# 1_-SOM-G3399.net
KiCad netlist of a schematic drawn in Altium Designer
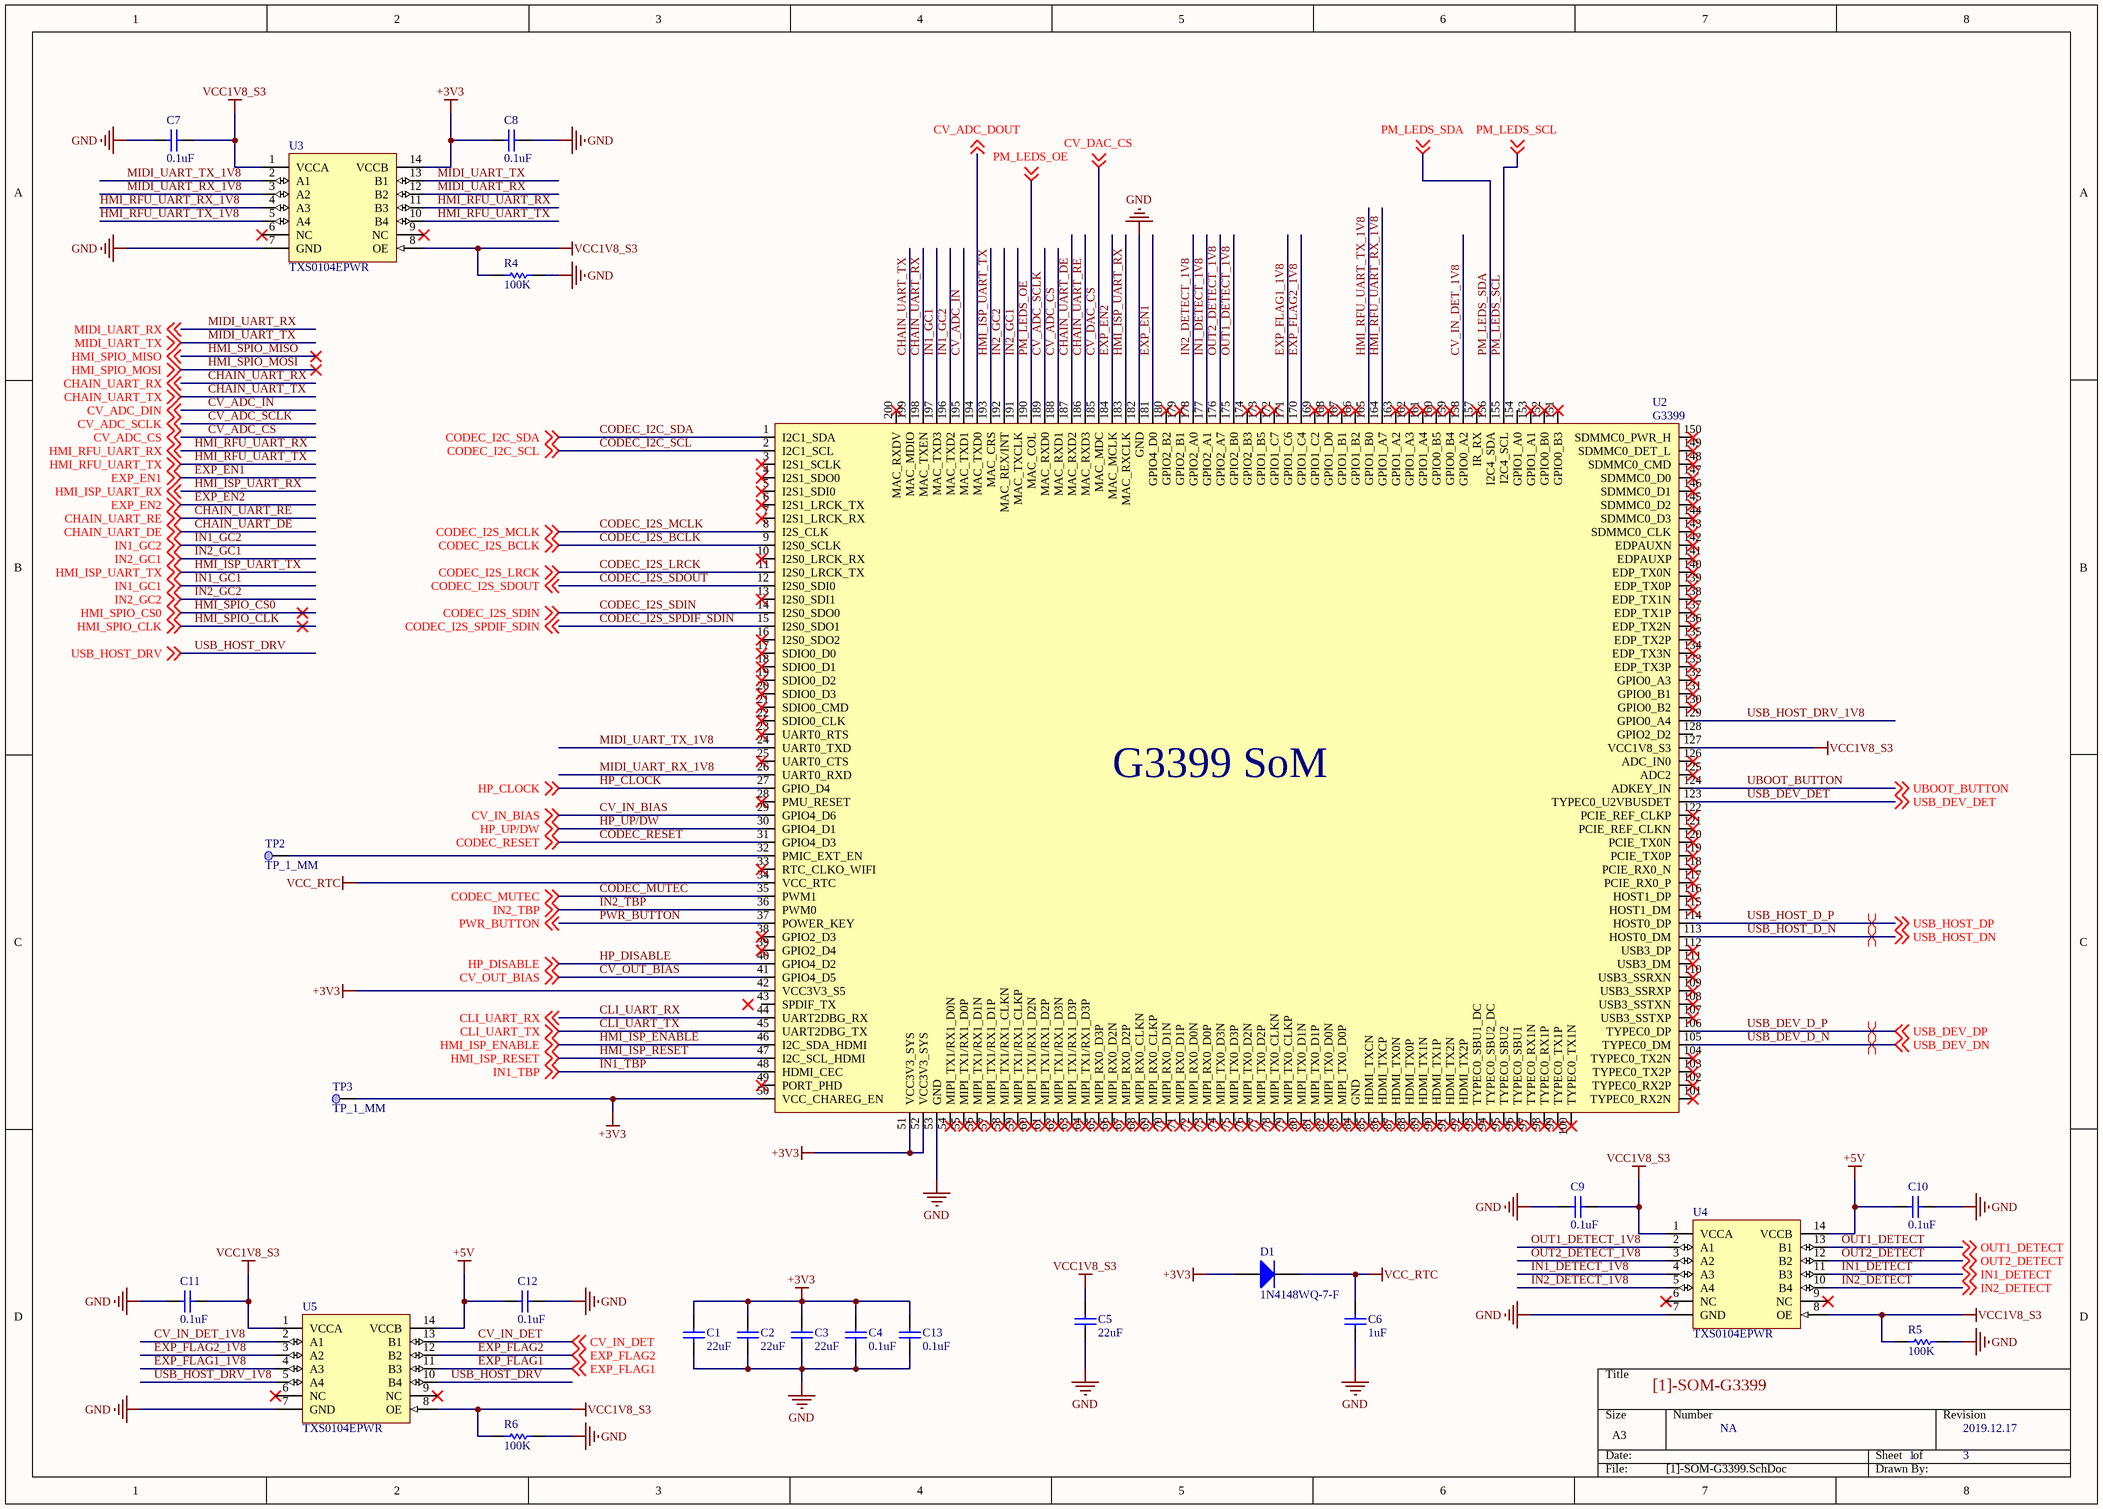
[diagram p0: [1]-SOM-G3399.SchDoc]

(export (version "E")
  (design (tool "Eeschema 10.0.6"))
  (components
    (comp (ref "C1")
      (value "22uF")
      (footprint "CAPC1608N")
      (description "CAP CER 22UF 6.3V X5R 0603")
      (fields (field (name "TOLERANCE") "20%"))
      (libsource (lib "bitsnio") (part "GRM188R60J226MEA0D"))
    )
    (comp (ref "C2")
      (value "22uF")
      (footprint "CAPC1608N")
      (description "CAP CER 22UF 6.3V X5R 0603")
      (fields (field (name "TOLERANCE") "20%"))
      (libsource (lib "bitsnio") (part "GRM188R60J226MEA0D"))
    )
    (comp (ref "C3")
      (value "22uF")
      (footprint "CAPC1608N")
      (description "CAP CER 22UF 6.3V X5R 0603")
      (fields (field (name "TOLERANCE") "20%"))
      (libsource (lib "bitsnio") (part "GRM188R60J226MEA0D"))
    )
    (comp (ref "C4")
      (value "0.1uF")
      (footprint "CAPC1005N")
      (description "CAP CER 0.1UF 50V X7R 0402")
      (fields (field (name "TOLERANCE") "10 %"))
      (libsource (lib "bitsnio") (part "GRM155R71H104KE14D"))
    )
    (comp (ref "C5")
      (value "22uF")
      (footprint "CAPC1608N")
      (description "CAP CER 22UF 6.3V X5R 0603")
      (fields (field (name "TOLERANCE") "20%"))
      (libsource (lib "bitsnio") (part "GRM188R60J226MEA0D"))
    )
    (comp (ref "C6")
      (value "1uF")
      (footprint "CAPC1005N")
      (description "CAP CER 1UF 6.3V X5R 0402")
      (fields (field (name "TOLERANCE") "±10%"))
      (libsource (lib "bitsnio") (part "C0402C105K9PACTU"))
    )
    (comp (ref "C7")
      (value "0.1uF")
      (footprint "CAPC1005N")
      (description "CAP CER 0.1UF 50V X7R 0402")
      (fields (field (name "TOLERANCE") "10 %"))
      (libsource (lib "bitsnio") (part "GRM155R71H104KE14D"))
    )
    (comp (ref "C8")
      (value "0.1uF")
      (footprint "CAPC1005N")
      (description "CAP CER 0.1UF 50V X7R 0402")
      (fields (field (name "TOLERANCE") "10 %"))
      (libsource (lib "bitsnio") (part "GRM155R71H104KE14D"))
    )
    (comp (ref "C9")
      (value "0.1uF")
      (footprint "CAPC1005N")
      (description "CAP CER 0.1UF 50V X7R 0402")
      (fields (field (name "TOLERANCE") "10 %"))
      (libsource (lib "bitsnio") (part "GRM155R71H104KE14D"))
    )
    (comp (ref "C10")
      (value "0.1uF")
      (footprint "CAPC1005N")
      (description "CAP CER 0.1UF 50V X7R 0402")
      (fields (field (name "TOLERANCE") "10 %"))
      (libsource (lib "bitsnio") (part "GRM155R71H104KE14D"))
    )
    (comp (ref "C11")
      (value "0.1uF")
      (footprint "CAPC1005N")
      (description "CAP CER 0.1UF 50V X7R 0402")
      (fields (field (name "TOLERANCE") "10 %"))
      (libsource (lib "bitsnio") (part "GRM155R71H104KE14D"))
    )
    (comp (ref "C12")
      (value "0.1uF")
      (footprint "CAPC1005N")
      (description "CAP CER 0.1UF 50V X7R 0402")
      (fields (field (name "TOLERANCE") "10 %"))
      (libsource (lib "bitsnio") (part "GRM155R71H104KE14D"))
    )
    (comp (ref "C13")
      (value "0.1uF")
      (footprint "CAPC1005N")
      (description "CAP CER 0.1UF 50V X7R 0402")
      (fields (field (name "TOLERANCE") "10 %"))
      (libsource (lib "bitsnio") (part "GRM155R71H104KE14D"))
    )
    (comp (ref "D1")
      (value "1N4148WQ-7-F")
      (footprint "SOD123")
      (description "DIODE GEN PURP 100V 300MA SOD123")
      (libsource (lib "bitsnio") (part "1N4148WQ-7-F"))
    )
    (comp (ref "R4")
      (value "100K")
      (footprint "RESC1005N")
      (description "RES SMD 100K OHM 1% 1/16W 0402")
      (fields (field (name "TOLERANCE") "1 %"))
      (libsource (lib "bitsnio") (part "RC0402FR-07100KL"))
    )
    (comp (ref "R5")
      (value "100K")
      (footprint "RESC1005N")
      (description "RES SMD 100K OHM 1% 1/16W 0402")
      (fields (field (name "TOLERANCE") "1 %"))
      (libsource (lib "bitsnio") (part "RC0402FR-07100KL"))
    )
    (comp (ref "R6")
      (value "100K")
      (footprint "RESC1005N")
      (description "RES SMD 100K OHM 1% 1/16W 0402")
      (fields (field (name "TOLERANCE") "1 %"))
      (libsource (lib "bitsnio") (part "RC0402FR-07100KL"))
    )
    (comp (ref "TP2") (value "TP_1_MM") (footprint "TP_1_MM") (libsource (lib "bitsnio") (part "TP_1_MM")))
    (comp (ref "TP3") (value "TP_1_MM") (footprint "TP_1_MM") (libsource (lib "bitsnio") (part "TP_1_MM")))
    (comp (ref "U2")
      (value "G3399")
      (footprint "G3399-MOD")
      (description "ROCKCHIP R3399 SoM")
      (libsource (lib "bitsnio") (part "G3399"))
    )
    (comp (ref "U3")
      (value "TXS0104EPWR")
      (footprint "TSSOP_PW14")
      (description "IC TRNSLTR BIDIRECTIONAL 14TSSOP")
      (libsource (lib "bitsnio") (part "IC_TXS0104EPWRG4"))
    )
    (comp (ref "U4")
      (value "TXS0104EPWR")
      (footprint "TSSOP_PW14")
      (description "IC TRNSLTR BIDIRECTIONAL 14TSSOP")
      (libsource (lib "bitsnio") (part "IC_TXS0104EPWRG4"))
    )
    (comp (ref "U5")
      (value "TXS0104EPWR")
      (footprint "TSSOP_PW14")
      (description "IC TRNSLTR BIDIRECTIONAL 14TSSOP")
      (libsource (lib "bitsnio") (part "IC_TXS0104EPWRG4"))
    )
  )
  (nets
    (net (code "1") (name "+3V3") (class "Default")
      (node (ref "C1") (pin "2") (pinfunction "2_2") (pintype "passive"))
      (node (ref "C13") (pin "2") (pinfunction "2_2") (pintype "passive"))
      (node (ref "C2") (pin "2") (pinfunction "2_2") (pintype "passive"))
      (node (ref "C3") (pin "2") (pinfunction "2_2") (pintype "passive"))
      (node (ref "C4") (pin "2") (pinfunction "2_2") (pintype "passive"))
      (node (ref "C8") (pin "2") (pinfunction "2_2") (pintype "passive"))
      (node (ref "D1") (pin "2") (pinfunction "A_2") (pintype "passive"))
      (node (ref "TP3") (pin "1") (pinfunction "1_1") (pintype "passive"))
      (node (ref "U2") (pin "42") (pinfunction "VCC3V3_S5_42") (pintype "passive"))
      (node (ref "U2") (pin "50") (pinfunction "VCC_CHAREG_EN_50") (pintype "passive"))
      (node (ref "U2") (pin "51") (pinfunction "VCC3V3_SYS_51") (pintype "passive"))
      (node (ref "U2") (pin "52") (pinfunction "VCC3V3_SYS_52") (pintype "passive"))
      (node (ref "U3") (pin "14") (pinfunction "VCCB_14") (pintype "power_in"))
    )
    (net (code "2") (name "+5V") (class "Default")
      (node (ref "C10") (pin "2") (pinfunction "2_2") (pintype "passive"))
      (node (ref "C12") (pin "2") (pinfunction "2_2") (pintype "passive"))
      (node (ref "U4") (pin "14") (pinfunction "VCCB_14") (pintype "power_in"))
      (node (ref "U5") (pin "14") (pinfunction "VCCB_14") (pintype "power_in"))
    )
    (net (code "3") (name "/CV_IN_DET_1V8") (class "Default")
      (node (ref "U2") (pin "158") (pinfunction "GPIO0_A2_158") (pintype "passive"))
      (node (ref "U5") (pin "2") (pinfunction "A1_2") (pintype "bidirectional"))
    )
    (net (code "4") (name "/EXP_FLAG1_1V8") (class "Default")
      (node (ref "U2") (pin "171") (pinfunction "GPIO1_C6_171") (pintype "passive"))
      (node (ref "U5") (pin "4") (pinfunction "A3_4") (pintype "bidirectional"))
    )
    (net (code "5") (name "/EXP_FLAG2_1V8") (class "Default")
      (node (ref "U2") (pin "170") (pinfunction "GPIO1_C4_170") (pintype "passive"))
      (node (ref "U5") (pin "3") (pinfunction "A2_3") (pintype "bidirectional"))
    )
    (net (code "6") (name "/HMI_RFU_UART_RX_1V8") (class "Default")
      (node (ref "U2") (pin "164") (pinfunction "GPIO1_A7_164") (pintype "passive"))
      (node (ref "U3") (pin "4") (pinfunction "A3_4") (pintype "bidirectional"))
    )
    (net (code "7") (name "/HMI_RFU_UART_TX_1V8") (class "Default")
      (node (ref "U2") (pin "165") (pinfunction "GPIO1_B0_165") (pintype "passive"))
      (node (ref "U3") (pin "5") (pinfunction "A4_5") (pintype "bidirectional"))
    )
    (net (code "8") (name "/IN1_DETECT_1V8") (class "Default")
      (node (ref "U2") (pin "177") (pinfunction "GPIO2_A1_177") (pintype "passive"))
      (node (ref "U4") (pin "4") (pinfunction "A3_4") (pintype "bidirectional"))
    )
    (net (code "9") (name "/IN2_DETECT_1V8") (class "Default")
      (node (ref "U2") (pin "178") (pinfunction "GPIO2_A0_178") (pintype "passive"))
      (node (ref "U4") (pin "5") (pinfunction "A4_5") (pintype "bidirectional"))
    )
    (net (code "10") (name "/MIDI_UART_RX_1V8") (class "Default")
      (node (ref "U2") (pin "26") (pinfunction "UART0_RXD_26") (pintype "passive"))
      (node (ref "U3") (pin "3") (pinfunction "A2_3") (pintype "bidirectional"))
    )
    (net (code "11") (name "/MIDI_UART_TX_1V8") (class "Default")
      (node (ref "U2") (pin "24") (pinfunction "UART0_TXD_24") (pintype "passive"))
      (node (ref "U3") (pin "2") (pinfunction "A1_2") (pintype "bidirectional"))
    )
    (net (code "12") (name "/OUT1_DETECT_1V8") (class "Default")
      (node (ref "U2") (pin "175") (pinfunction "GPIO2_B0_175") (pintype "passive"))
      (node (ref "U4") (pin "2") (pinfunction "A1_2") (pintype "bidirectional"))
    )
    (net (code "13") (name "/OUT2_DETECT_1V8") (class "Default")
      (node (ref "U2") (pin "176") (pinfunction "GPIO2_A7_176") (pintype "passive"))
      (node (ref "U4") (pin "3") (pinfunction "A2_3") (pintype "bidirectional"))
    )
    (net (code "14") (name "/USB_HOST_DRV_1V8") (class "Default")
      (node (ref "U2") (pin "129") (pinfunction "GPIO0_A4_129") (pintype "passive"))
      (node (ref "U5") (pin "5") (pinfunction "A4_5") (pintype "bidirectional"))
    )
    (net (code "15") (name "CHAIN_UART_DE") (class "Default")
      (node (ref "U2") (pin "187") (pinfunction "MAC_RXD2_187") (pintype "passive"))
    )
    (net (code "16") (name "CHAIN_UART_RE") (class "Default")
      (node (ref "U2") (pin "186") (pinfunction "MAC_RXD3_186") (pintype "passive"))
    )
    (net (code "17") (name "CHAIN_UART_RX") (class "Default")
      (node (ref "U2") (pin "198") (pinfunction "MAC_TXEN_198") (pintype "passive"))
    )
    (net (code "18") (name "CHAIN_UART_TX") (class "Default")
      (node (ref "U2") (pin "199") (pinfunction "MAC_MDIO_199") (pintype "passive"))
    )
    (net (code "19") (name "CLI_UART_RX") (class "Default")
      (node (ref "U2") (pin "44") (pinfunction "UART2DBG_RX_44") (pintype "passive"))
    )
    (net (code "20") (name "CLI_UART_TX") (class "Default")
      (node (ref "U2") (pin "45") (pinfunction "UART2DBG_TX_45") (pintype "passive"))
    )
    (net (code "21") (name "CODEC_I2C_SCL") (class "Default")
      (node (ref "U2") (pin "2") (pinfunction "I2C1_SCL_2") (pintype "passive"))
    )
    (net (code "22") (name "CODEC_I2C_SDA") (class "Default")
      (node (ref "U2") (pin "1") (pinfunction "I2C1_SDA_1") (pintype "passive"))
    )
    (net (code "23") (name "CODEC_I2S_BCLK") (class "Default")
      (node (ref "U2") (pin "9") (pinfunction "I2S0_SCLK_9") (pintype "passive"))
    )
    (net (code "24") (name "CODEC_I2S_LRCK") (class "Default")
      (node (ref "U2") (pin "11") (pinfunction "I2S0_LRCK_TX_11") (pintype "passive"))
    )
    (net (code "25") (name "CODEC_I2S_MCLK") (class "Default")
      (node (ref "U2") (pin "8") (pinfunction "I2S_CLK_8") (pintype "passive"))
    )
    (net (code "26") (name "CODEC_I2S_SDIN") (class "Default")
      (node (ref "U2") (pin "14") (pinfunction "I2S0_SDO0_14") (pintype "passive"))
    )
    (net (code "27") (name "CODEC_I2S_SDOUT") (class "Default")
      (node (ref "U2") (pin "12") (pinfunction "I2S0_SDI0_12") (pintype "passive"))
    )
    (net (code "28") (name "CODEC_I2S_SPDIF_SDIN") (class "Default")
      (node (ref "U2") (pin "15") (pinfunction "I2S0_SDO1_15") (pintype "passive"))
    )
    (net (code "29") (name "CODEC_MUTEC") (class "Default")
      (node (ref "U2") (pin "35") (pinfunction "PWM1_35") (pintype "passive"))
    )
    (net (code "30") (name "CODEC_RESET") (class "Default")
      (node (ref "U2") (pin "31") (pinfunction "GPIO4_D3_31") (pintype "passive"))
    )
    (net (code "31") (name "CV_ADC_CS") (class "Default")
      (node (ref "U2") (pin "188") (pinfunction "MAC_RXD1_188") (pintype "passive"))
    )
    (net (code "32") (name "CV_ADC_DIN") (class "Default")
      (node (ref "U2") (pin "195") (pinfunction "MAC_TXD1_195") (pintype "passive"))
    )
    (net (code "33") (name "CV_ADC_DOUT") (class "Default")
      (node (ref "U2") (pin "194") (pinfunction "MAC_TXD0_194") (pintype "passive"))
    )
    (net (code "34") (name "CV_ADC_SCLK") (class "Default")
      (node (ref "U2") (pin "189") (pinfunction "MAC_RXD0_189") (pintype "passive"))
    )
    (net (code "35") (name "CV_DAC_CS") (class "Default")
      (node (ref "U2") (pin "185") (pinfunction "MAC_MDC_185") (pintype "passive"))
    )
    (net (code "36") (name "CV_IN_BIAS") (class "Default")
      (node (ref "U2") (pin "29") (pinfunction "GPIO4_D6_29") (pintype "passive"))
    )
    (net (code "37") (name "CV_IN_DET") (class "Default")
      (node (ref "U5") (pin "13") (pinfunction "B1_13") (pintype "bidirectional"))
    )
    (net (code "38") (name "CV_OUT_BIAS") (class "Default")
      (node (ref "U2") (pin "41") (pinfunction "GPIO4_D5_41") (pintype "passive"))
    )
    (net (code "39") (name "EXP_EN1") (class "Default")
      (node (ref "U2") (pin "181") (pinfunction "GPIO4_D0_181") (pintype "passive"))
    )
    (net (code "40") (name "EXP_EN2") (class "Default")
      (node (ref "U2") (pin "184") (pinfunction "MAC_MCLK_184") (pintype "passive"))
    )
    (net (code "41") (name "EXP_FLAG1") (class "Default")
      (node (ref "U5") (pin "11") (pinfunction "B3_11") (pintype "bidirectional"))
    )
    (net (code "42") (name "EXP_FLAG2") (class "Default")
      (node (ref "U5") (pin "12") (pinfunction "B2_12") (pintype "bidirectional"))
    )
    (net (code "43") (name "GND") (class "Default")
      (node (ref "C1") (pin "1") (pinfunction "1_1") (pintype "passive"))
      (node (ref "C10") (pin "1") (pinfunction "1_1") (pintype "passive"))
      (node (ref "C11") (pin "1") (pinfunction "1_1") (pintype "passive"))
      (node (ref "C12") (pin "1") (pinfunction "1_1") (pintype "passive"))
      (node (ref "C13") (pin "1") (pinfunction "1_1") (pintype "passive"))
      (node (ref "C2") (pin "1") (pinfunction "1_1") (pintype "passive"))
      (node (ref "C3") (pin "1") (pinfunction "1_1") (pintype "passive"))
      (node (ref "C4") (pin "1") (pinfunction "1_1") (pintype "passive"))
      (node (ref "C5") (pin "1") (pinfunction "1_1") (pintype "passive"))
      (node (ref "C6") (pin "1") (pinfunction "1_1") (pintype "passive"))
      (node (ref "C7") (pin "1") (pinfunction "1_1") (pintype "passive"))
      (node (ref "C8") (pin "1") (pinfunction "1_1") (pintype "passive"))
      (node (ref "C9") (pin "1") (pinfunction "1_1") (pintype "passive"))
      (node (ref "R4") (pin "2") (pinfunction "2_2") (pintype "passive"))
      (node (ref "R5") (pin "2") (pinfunction "2_2") (pintype "passive"))
      (node (ref "R6") (pin "1") (pinfunction "1_1") (pintype "passive"))
      (node (ref "U2") (pin "182") (pinfunction "GND_182") (pintype "passive"))
      (node (ref "U2") (pin "53") (pinfunction "GND_53") (pintype "passive"))
      (node (ref "U3") (pin "7") (pinfunction "GND_7") (pintype "power_in"))
      (node (ref "U4") (pin "7") (pinfunction "GND_7") (pintype "power_in"))
      (node (ref "U5") (pin "7") (pinfunction "GND_7") (pintype "power_in"))
    )
    (net (code "44") (name "HMI_ISP_ENABLE") (class "Default")
      (node (ref "U2") (pin "46") (pinfunction "I2C_SDA_HDMI_46") (pintype "passive"))
    )
    (net (code "45") (name "HMI_ISP_RESET") (class "Default")
      (node (ref "U2") (pin "47") (pinfunction "I2C_SCL_HDMI_47") (pintype "passive"))
    )
    (net (code "46") (name "HMI_ISP_UART_RX") (class "Default")
      (node (ref "U2") (pin "183") (pinfunction "MAC_RXCLK_183") (pintype "passive"))
    )
    (net (code "47") (name "HMI_ISP_UART_TX") (class "Default")
      (node (ref "U2") (pin "193") (pinfunction "MAC_CRS_193") (pintype "passive"))
    )
    (net (code "48") (name "HMI_RFU_UART_RX") (class "Default")
      (node (ref "U3") (pin "11") (pinfunction "B3_11") (pintype "bidirectional"))
    )
    (net (code "49") (name "HMI_RFU_UART_TX") (class "Default")
      (node (ref "U3") (pin "10") (pinfunction "B4_10") (pintype "bidirectional"))
    )
    (net (code "54") (name "HP_CLOCK") (class "Default")
      (node (ref "U2") (pin "27") (pinfunction "GPIO_D4_27") (pintype "passive"))
    )
    (net (code "55") (name "HP_DISABLE") (class "Default")
      (node (ref "U2") (pin "40") (pinfunction "GPIO4_D2_40") (pintype "passive"))
    )
    (net (code "56") (name "HP_UP{slash}DW") (class "Default")
      (node (ref "U2") (pin "30") (pinfunction "GPIO4_D1_30") (pintype "passive"))
    )
    (net (code "57") (name "IN1_DETECT") (class "Default")
      (node (ref "U4") (pin "11") (pinfunction "B3_11") (pintype "bidirectional"))
    )
    (net (code "58") (name "IN1_GC1") (class "Default")
      (node (ref "U2") (pin "197") (pinfunction "MAC_TXD3_197") (pintype "passive"))
    )
    (net (code "59") (name "IN1_GC2") (class "Default")
      (node (ref "U2") (pin "196") (pinfunction "MAC_TXD2_196") (pintype "passive"))
    )
    (net (code "60") (name "IN1_TBP") (class "Default")
      (node (ref "U2") (pin "48") (pinfunction "HDMI_CEC_48") (pintype "passive"))
    )
    (net (code "61") (name "IN2_DETECT") (class "Default")
      (node (ref "U4") (pin "10") (pinfunction "B4_10") (pintype "bidirectional"))
    )
    (net (code "62") (name "IN2_GC1") (class "Default")
      (node (ref "U2") (pin "191") (pinfunction "MAC_TXCLK_191") (pintype "passive"))
    )
    (net (code "63") (name "IN2_GC2") (class "Default")
      (node (ref "U2") (pin "192") (pinfunction "MAC_REX/INT_192") (pintype "passive"))
    )
    (net (code "64") (name "IN2_TBP") (class "Default")
      (node (ref "U2") (pin "36") (pinfunction "PWM0_36") (pintype "passive"))
    )
    (net (code "65") (name "MIDI_UART_RX") (class "Default")
      (node (ref "U3") (pin "12") (pinfunction "B2_12") (pintype "bidirectional"))
    )
    (net (code "66") (name "MIDI_UART_TX") (class "Default")
      (node (ref "U3") (pin "13") (pinfunction "B1_13") (pintype "bidirectional"))
    )
    (net (code "67") (name "Net-(U2-PMIC_EXT_EN)") (class "Default")
      (node (ref "TP2") (pin "1") (pinfunction "1_1") (pintype "passive"))
      (node (ref "U2") (pin "32") (pinfunction "PMIC_EXT_EN_32") (pintype "passive"))
    )
    (net (code "68") (name "OUT1_DETECT") (class "Default")
      (node (ref "U4") (pin "13") (pinfunction "B1_13") (pintype "bidirectional"))
    )
    (net (code "69") (name "OUT2_DETECT") (class "Default")
      (node (ref "U4") (pin "12") (pinfunction "B2_12") (pintype "bidirectional"))
    )
    (net (code "70") (name "PM_LEDS_OE") (class "Default")
      (node (ref "U2") (pin "190") (pinfunction "MAC_COL_190") (pintype "passive"))
    )
    (net (code "71") (name "PM_LEDS_SCL") (class "Default")
      (node (ref "U2") (pin "155") (pinfunction "I2C4_SCL_155") (pintype "passive"))
    )
    (net (code "72") (name "PM_LEDS_SDA") (class "Default")
      (node (ref "U2") (pin "156") (pinfunction "I2C4_SDA_156") (pintype "passive"))
    )
    (net (code "73") (name "PWR_BUTTON") (class "Default")
      (node (ref "U2") (pin "37") (pinfunction "POWER_KEY_37") (pintype "passive"))
    )
    (net (code "74") (name "UBOOT_BUTTON") (class "Default")
      (node (ref "U2") (pin "124") (pinfunction "ADKEY_IN_124") (pintype "passive"))
    )
    (net (code "75") (name "USB_DEV_DET") (class "Default")
      (node (ref "U2") (pin "123") (pinfunction "TYPEC0_U2VBUSDET_123") (pintype "passive"))
    )
    (net (code "76") (name "USB_DEV_DN") (class "Default")
      (node (ref "U2") (pin "105") (pinfunction "TYPEC0_DM_105") (pintype "passive"))
    )
    (net (code "77") (name "USB_DEV_DP") (class "Default")
      (node (ref "U2") (pin "106") (pinfunction "TYPEC0_DP_106") (pintype "passive"))
    )
    (net (code "78") (name "USB_HOST_DN") (class "Default")
      (node (ref "U2") (pin "113") (pinfunction "HOST0_DM_113") (pintype "passive"))
    )
    (net (code "79") (name "USB_HOST_DP") (class "Default")
      (node (ref "U2") (pin "114") (pinfunction "HOST0_DP_114") (pintype "passive"))
    )
    (net (code "80") (name "USB_HOST_DRV") (class "Default")
      (node (ref "U5") (pin "10") (pinfunction "B4_10") (pintype "bidirectional"))
    )
    (net (code "81") (name "VCC1V8_S3") (class "Default")
      (node (ref "C11") (pin "2") (pinfunction "2_2") (pintype "passive"))
      (node (ref "C5") (pin "2") (pinfunction "2_2") (pintype "passive"))
      (node (ref "C7") (pin "2") (pinfunction "2_2") (pintype "passive"))
      (node (ref "C9") (pin "2") (pinfunction "2_2") (pintype "passive"))
      (node (ref "R4") (pin "1") (pinfunction "1_1") (pintype "passive"))
      (node (ref "R5") (pin "1") (pinfunction "1_1") (pintype "passive"))
      (node (ref "R6") (pin "2") (pinfunction "2_2") (pintype "passive"))
      (node (ref "U2") (pin "127") (pinfunction "VCC1V8_S3_127") (pintype "passive"))
      (node (ref "U3") (pin "1") (pinfunction "VCCA_1") (pintype "power_in"))
      (node (ref "U3") (pin "8") (pinfunction "OE_8") (pintype "input"))
      (node (ref "U4") (pin "1") (pinfunction "VCCA_1") (pintype "power_in"))
      (node (ref "U4") (pin "8") (pinfunction "OE_8") (pintype "input"))
      (node (ref "U5") (pin "1") (pinfunction "VCCA_1") (pintype "power_in"))
      (node (ref "U5") (pin "8") (pinfunction "OE_8") (pintype "input"))
    )
    (net (code "82") (name "VCC_RTC") (class "Default")
      (node (ref "C6") (pin "2") (pinfunction "2_2") (pintype "passive"))
      (node (ref "D1") (pin "1") (pinfunction "K_1") (pintype "passive"))
      (node (ref "U2") (pin "34") (pinfunction "VCC_RTC_34") (pintype "passive"))
    )
    (net (code "83") (name "unconnected-(U2-ADC2-Pad125)") (class "Default")
      (node (ref "U2") (pin "125") (pinfunction "ADC2_125") (pintype "passive+no_connect"))
    )
    (net (code "84") (name "unconnected-(U2-ADC_IN0-Pad126)") (class "Default")
      (node (ref "U2") (pin "126") (pinfunction "ADC_IN0_126") (pintype "passive+no_connect"))
    )
    (net (code "85") (name "unconnected-(U2-EDPAUXN-Pad142)") (class "Default")
      (node (ref "U2") (pin "142") (pinfunction "EDPAUXN_142") (pintype "passive+no_connect"))
    )
    (net (code "86") (name "unconnected-(U2-EDPAUXP-Pad141)") (class "Default")
      (node (ref "U2") (pin "141") (pinfunction "EDPAUXP_141") (pintype "passive+no_connect"))
    )
    (net (code "87") (name "unconnected-(U2-EDP_TX0N-Pad140)") (class "Default")
      (node (ref "U2") (pin "140") (pinfunction "EDP_TX0N_140") (pintype "passive+no_connect"))
    )
    (net (code "88") (name "unconnected-(U2-EDP_TX0P-Pad139)") (class "Default")
      (node (ref "U2") (pin "139") (pinfunction "EDP_TX0P_139") (pintype "passive+no_connect"))
    )
    (net (code "89") (name "unconnected-(U2-EDP_TX1N-Pad138)") (class "Default")
      (node (ref "U2") (pin "138") (pinfunction "EDP_TX1N_138") (pintype "passive+no_connect"))
    )
    (net (code "90") (name "unconnected-(U2-EDP_TX1P-Pad137)") (class "Default")
      (node (ref "U2") (pin "137") (pinfunction "EDP_TX1P_137") (pintype "passive+no_connect"))
    )
    (net (code "91") (name "unconnected-(U2-EDP_TX2N-Pad136)") (class "Default")
      (node (ref "U2") (pin "136") (pinfunction "EDP_TX2N_136") (pintype "passive+no_connect"))
    )
    (net (code "92") (name "unconnected-(U2-EDP_TX2P-Pad135)") (class "Default")
      (node (ref "U2") (pin "135") (pinfunction "EDP_TX2P_135") (pintype "passive+no_connect"))
    )
    (net (code "93") (name "unconnected-(U2-EDP_TX3N-Pad134)") (class "Default")
      (node (ref "U2") (pin "134") (pinfunction "EDP_TX3N_134") (pintype "passive+no_connect"))
    )
    (net (code "94") (name "unconnected-(U2-EDP_TX3P-Pad133)") (class "Default")
      (node (ref "U2") (pin "133") (pinfunction "EDP_TX3P_133") (pintype "passive+no_connect"))
    )
    (net (code "95") (name "unconnected-(U2-GND-Pad84)") (class "Default")
      (node (ref "U2") (pin "84") (pinfunction "GND_84") (pintype "passive+no_connect"))
    )
    (net (code "96") (name "unconnected-(U2-GPIO0_A3-Pad132)") (class "Default")
      (node (ref "U2") (pin "132") (pinfunction "GPIO0_A3_132") (pintype "passive+no_connect"))
    )
    (net (code "97") (name "unconnected-(U2-GPIO0_B0-Pad152)") (class "Default")
      (node (ref "U2") (pin "152") (pinfunction "GPIO0_B0_152") (pintype "passive+no_connect"))
    )
    (net (code "98") (name "unconnected-(U2-GPIO0_B1-Pad131)") (class "Default")
      (node (ref "U2") (pin "131") (pinfunction "GPIO0_B1_131") (pintype "passive+no_connect"))
    )
    (net (code "99") (name "unconnected-(U2-GPIO0_B2-Pad130)") (class "Default")
      (node (ref "U2") (pin "130") (pinfunction "GPIO0_B2_130") (pintype "passive+no_connect"))
    )
    (net (code "100") (name "unconnected-(U2-GPIO0_B3-Pad151)") (class "Default")
      (node (ref "U2") (pin "151") (pinfunction "GPIO0_B3_151") (pintype "passive+no_connect"))
    )
    (net (code "101") (name "unconnected-(U2-GPIO0_B4-Pad159)") (class "Default")
      (node (ref "U2") (pin "159") (pinfunction "GPIO0_B4_159") (pintype "passive+no_connect"))
    )
    (net (code "102") (name "unconnected-(U2-GPIO0_B5-Pad160)") (class "Default")
      (node (ref "U2") (pin "160") (pinfunction "GPIO0_B5_160") (pintype "passive+no_connect"))
    )
    (net (code "103") (name "unconnected-(U2-GPIO1_A0-Pad154)") (class "Default")
      (node (ref "U2") (pin "154") (pinfunction "GPIO1_A0_154") (pintype "passive"))
    )
    (net (code "104") (name "unconnected-(U2-GPIO1_A1-Pad153)") (class "Default")
      (node (ref "U2") (pin "153") (pinfunction "GPIO1_A1_153") (pintype "passive+no_connect"))
    )
    (net (code "105") (name "unconnected-(U2-GPIO1_A2-Pad163)") (class "Default")
      (node (ref "U2") (pin "163") (pinfunction "GPIO1_A2_163") (pintype "passive+no_connect"))
    )
    (net (code "106") (name "unconnected-(U2-GPIO1_A3-Pad162)") (class "Default")
      (node (ref "U2") (pin "162") (pinfunction "GPIO1_A3_162") (pintype "passive+no_connect"))
    )
    (net (code "107") (name "unconnected-(U2-GPIO1_A4-Pad161)") (class "Default")
      (node (ref "U2") (pin "161") (pinfunction "GPIO1_A4_161") (pintype "passive+no_connect"))
    )
    (net (code "108") (name "unconnected-(U2-GPIO1_B1-Pad167)") (class "Default")
      (node (ref "U2") (pin "167") (pinfunction "GPIO1_B1_167") (pintype "passive+no_connect"))
    )
    (net (code "109") (name "unconnected-(U2-GPIO1_B2-Pad166)") (class "Default")
      (node (ref "U2") (pin "166") (pinfunction "GPIO1_B2_166") (pintype "passive+no_connect"))
    )
    (net (code "110") (name "unconnected-(U2-GPIO1_B5-Pad173)") (class "Default")
      (node (ref "U2") (pin "173") (pinfunction "GPIO1_B5_173") (pintype "passive+no_connect"))
    )
    (net (code "111") (name "unconnected-(U2-GPIO1_C2-Pad169)") (class "Default")
      (node (ref "U2") (pin "169") (pinfunction "GPIO1_C2_169") (pintype "passive+no_connect"))
    )
    (net (code "112") (name "unconnected-(U2-GPIO1_C7-Pad172)") (class "Default")
      (node (ref "U2") (pin "172") (pinfunction "GPIO1_C7_172") (pintype "passive+no_connect"))
    )
    (net (code "113") (name "unconnected-(U2-GPIO1_D0-Pad168)") (class "Default")
      (node (ref "U2") (pin "168") (pinfunction "GPIO1_D0_168") (pintype "passive+no_connect"))
    )
    (net (code "114") (name "unconnected-(U2-GPIO2_B1-Pad179)") (class "Default")
      (node (ref "U2") (pin "179") (pinfunction "GPIO2_B1_179") (pintype "passive+no_connect"))
    )
    (net (code "115") (name "unconnected-(U2-GPIO2_B2-Pad180)") (class "Default")
      (node (ref "U2") (pin "180") (pinfunction "GPIO2_B2_180") (pintype "passive+no_connect"))
    )
    (net (code "116") (name "unconnected-(U2-GPIO2_B3-Pad174)") (class "Default")
      (node (ref "U2") (pin "174") (pinfunction "GPIO2_B3_174") (pintype "passive+no_connect"))
    )
    (net (code "117") (name "unconnected-(U2-GPIO2_D2-Pad128)") (class "Default")
      (node (ref "U2") (pin "128") (pinfunction "GPIO2_D2_128") (pintype "passive"))
    )
    (net (code "118") (name "unconnected-(U2-GPIO2_D3-Pad38)") (class "Default")
      (node (ref "U2") (pin "38") (pinfunction "GPIO2_D3_38") (pintype "passive+no_connect"))
    )
    (net (code "119") (name "unconnected-(U2-GPIO2_D4-Pad39)") (class "Default")
      (node (ref "U2") (pin "39") (pinfunction "GPIO2_D4_39") (pintype "passive+no_connect"))
    )
    (net (code "120") (name "unconnected-(U2-HDMI_TX0N-Pad87)") (class "Default")
      (node (ref "U2") (pin "87") (pinfunction "HDMI_TX0N_87") (pintype "passive+no_connect"))
    )
    (net (code "121") (name "unconnected-(U2-HDMI_TX0P-Pad88)") (class "Default")
      (node (ref "U2") (pin "88") (pinfunction "HDMI_TX0P_88") (pintype "passive+no_connect"))
    )
    (net (code "122") (name "unconnected-(U2-HDMI_TX1N-Pad89)") (class "Default")
      (node (ref "U2") (pin "89") (pinfunction "HDMI_TX1N_89") (pintype "passive+no_connect"))
    )
    (net (code "123") (name "unconnected-(U2-HDMI_TX1P-Pad90)") (class "Default")
      (node (ref "U2") (pin "90") (pinfunction "HDMI_TX1P_90") (pintype "passive+no_connect"))
    )
    (net (code "124") (name "unconnected-(U2-HDMI_TX2N-Pad91)") (class "Default")
      (node (ref "U2") (pin "91") (pinfunction "HDMI_TX2N_91") (pintype "passive+no_connect"))
    )
    (net (code "125") (name "unconnected-(U2-HDMI_TX2P-Pad92)") (class "Default")
      (node (ref "U2") (pin "92") (pinfunction "HDMI_TX2P_92") (pintype "passive+no_connect"))
    )
    (net (code "126") (name "unconnected-(U2-HDMI_TXCN-Pad85)") (class "Default")
      (node (ref "U2") (pin "85") (pinfunction "HDMI_TXCN_85") (pintype "passive+no_connect"))
    )
    (net (code "127") (name "unconnected-(U2-HDMI_TXCP-Pad86)") (class "Default")
      (node (ref "U2") (pin "86") (pinfunction "HDMI_TXCP_86") (pintype "passive+no_connect"))
    )
    (net (code "128") (name "unconnected-(U2-HOST1_DM-Pad115)") (class "Default")
      (node (ref "U2") (pin "115") (pinfunction "HOST1_DM_115") (pintype "passive+no_connect"))
    )
    (net (code "129") (name "unconnected-(U2-HOST1_DP-Pad116)") (class "Default")
      (node (ref "U2") (pin "116") (pinfunction "HOST1_DP_116") (pintype "passive+no_connect"))
    )
    (net (code "130") (name "unconnected-(U2-I2S0_LRCK_RX-Pad10)") (class "Default")
      (node (ref "U2") (pin "10") (pinfunction "I2S0_LRCK_RX_10") (pintype "passive+no_connect"))
    )
    (net (code "131") (name "unconnected-(U2-I2S0_SDI1-Pad13)") (class "Default")
      (node (ref "U2") (pin "13") (pinfunction "I2S0_SDI1_13") (pintype "passive+no_connect"))
    )
    (net (code "132") (name "unconnected-(U2-I2S0_SDO2-Pad16)") (class "Default")
      (node (ref "U2") (pin "16") (pinfunction "I2S0_SDO2_16") (pintype "passive+no_connect"))
    )
    (net (code "133") (name "unconnected-(U2-I2S1_LRCK_RX-Pad7)") (class "Default")
      (node (ref "U2") (pin "7") (pinfunction "I2S1_LRCK_RX_7") (pintype "passive+no_connect"))
    )
    (net (code "134") (name "unconnected-(U2-I2S1_LRCK_TX-Pad6)") (class "Default")
      (node (ref "U2") (pin "6") (pinfunction "I2S1_LRCK_TX_6") (pintype "passive+no_connect"))
    )
    (net (code "135") (name "unconnected-(U2-I2S1_SCLK-Pad3)") (class "Default")
      (node (ref "U2") (pin "3") (pinfunction "I2S1_SCLK_3") (pintype "passive+no_connect"))
    )
    (net (code "136") (name "unconnected-(U2-I2S1_SDI0-Pad5)") (class "Default")
      (node (ref "U2") (pin "5") (pinfunction "I2S1_SDI0_5") (pintype "passive+no_connect"))
    )
    (net (code "137") (name "unconnected-(U2-I2S1_SDO0-Pad4)") (class "Default")
      (node (ref "U2") (pin "4") (pinfunction "I2S1_SDO0_4") (pintype "passive+no_connect"))
    )
    (net (code "138") (name "unconnected-(U2-IR_RX-Pad157)") (class "Default")
      (node (ref "U2") (pin "157") (pinfunction "IR_RX_157") (pintype "passive+no_connect"))
    )
    (net (code "139") (name "unconnected-(U2-MAC_RXDV-Pad200)") (class "Default")
      (node (ref "U2") (pin "200") (pinfunction "MAC_RXDV_200") (pintype "passive+no_connect"))
    )
    (net (code "140") (name "unconnected-(U2-MIPI_RX0_CLKN-Pad68)") (class "Default")
      (node (ref "U2") (pin "68") (pinfunction "MIPI_RX0_CLKN_68") (pintype "passive+no_connect"))
    )
    (net (code "141") (name "unconnected-(U2-MIPI_RX0_CLKP-Pad69)") (class "Default")
      (node (ref "U2") (pin "69") (pinfunction "MIPI_RX0_CLKP_69") (pintype "passive+no_connect"))
    )
    (net (code "142") (name "unconnected-(U2-MIPI_RX0_D0N-Pad72)") (class "Default")
      (node (ref "U2") (pin "72") (pinfunction "MIPI_RX0_D0N_72") (pintype "passive+no_connect"))
    )
    (net (code "143") (name "unconnected-(U2-MIPI_RX0_D0P-Pad73)") (class "Default")
      (node (ref "U2") (pin "73") (pinfunction "MIPI_RX0_D0P_73") (pintype "passive+no_connect"))
    )
    (net (code "144") (name "unconnected-(U2-MIPI_RX0_D1N-Pad70)") (class "Default")
      (node (ref "U2") (pin "70") (pinfunction "MIPI_RX0_D1N_70") (pintype "passive+no_connect"))
    )
    (net (code "145") (name "unconnected-(U2-MIPI_RX0_D1P-Pad71)") (class "Default")
      (node (ref "U2") (pin "71") (pinfunction "MIPI_RX0_D1P_71") (pintype "passive+no_connect"))
    )
    (net (code "146") (name "unconnected-(U2-MIPI_RX0_D2N-Pad66)") (class "Default")
      (node (ref "U2") (pin "66") (pinfunction "MIPI_RX0_D2N_66") (pintype "passive+no_connect"))
    )
    (net (code "147") (name "unconnected-(U2-MIPI_RX0_D2P-Pad67)") (class "Default")
      (node (ref "U2") (pin "67") (pinfunction "MIPI_RX0_D2P_67") (pintype "passive+no_connect"))
    )
    (net (code "148") (name "unconnected-(U2-MIPI_RX0_D3P-Pad65)") (class "Default")
      (node (ref "U2") (pin "65") (pinfunction "MIPI_RX0_D3P_65") (pintype "passive+no_connect"))
    )
    (net (code "149") (name "unconnected-(U2-MIPI_TX0_CLKN-Pad78)") (class "Default")
      (node (ref "U2") (pin "78") (pinfunction "MIPI_TX0_CLKN_78") (pintype "passive+no_connect"))
    )
    (net (code "150") (name "unconnected-(U2-MIPI_TX0_CLKP-Pad79)") (class "Default")
      (node (ref "U2") (pin "79") (pinfunction "MIPI_TX0_CLKP_79") (pintype "passive+no_connect"))
    )
    (net (code "151") (name "unconnected-(U2-MIPI_TX0_D0N-Pad82)") (class "Default")
      (node (ref "U2") (pin "82") (pinfunction "MIPI_TX0_D0N_82") (pintype "passive+no_connect"))
    )
    (net (code "152") (name "unconnected-(U2-MIPI_TX0_D0P-Pad83)") (class "Default")
      (node (ref "U2") (pin "83") (pinfunction "MIPI_TX0_D0P_83") (pintype "passive+no_connect"))
    )
    (net (code "153") (name "unconnected-(U2-MIPI_TX0_D1N-Pad80)") (class "Default")
      (node (ref "U2") (pin "80") (pinfunction "MIPI_TX0_D1N_80") (pintype "passive+no_connect"))
    )
    (net (code "154") (name "unconnected-(U2-MIPI_TX0_D1P-Pad81)") (class "Default")
      (node (ref "U2") (pin "81") (pinfunction "MIPI_TX0_D1P_81") (pintype "passive+no_connect"))
    )
    (net (code "155") (name "unconnected-(U2-MIPI_TX0_D2N-Pad76)") (class "Default")
      (node (ref "U2") (pin "76") (pinfunction "MIPI_TX0_D2N_76") (pintype "passive+no_connect"))
    )
    (net (code "156") (name "unconnected-(U2-MIPI_TX0_D2P-Pad77)") (class "Default")
      (node (ref "U2") (pin "77") (pinfunction "MIPI_TX0_D2P_77") (pintype "passive+no_connect"))
    )
    (net (code "157") (name "unconnected-(U2-MIPI_TX0_D3N-Pad74)") (class "Default")
      (node (ref "U2") (pin "74") (pinfunction "MIPI_TX0_D3N_74") (pintype "passive+no_connect"))
    )
    (net (code "158") (name "unconnected-(U2-MIPI_TX0_D3P-Pad75)") (class "Default")
      (node (ref "U2") (pin "75") (pinfunction "MIPI_TX0_D3P_75") (pintype "passive+no_connect"))
    )
    (net (code "159") (name "unconnected-(U2-MIPI_TX1{slash}RX1_CLKN-Pad58)") (class "Default")
      (node (ref "U2") (pin "58") (pinfunction "MIPI_TX1/RX1_CLKN_58") (pintype "passive+no_connect"))
    )
    (net (code "160") (name "unconnected-(U2-MIPI_TX1{slash}RX1_CLKP-Pad59)") (class "Default")
      (node (ref "U2") (pin "59") (pinfunction "MIPI_TX1/RX1_CLKP_59") (pintype "passive+no_connect"))
    )
    (net (code "161") (name "unconnected-(U2-MIPI_TX1{slash}RX1_D0N-Pad54)") (class "Default")
      (node (ref "U2") (pin "54") (pinfunction "MIPI_TX1/RX1_D0N_54") (pintype "passive+no_connect"))
    )
    (net (code "162") (name "unconnected-(U2-MIPI_TX1{slash}RX1_D0P-Pad55)") (class "Default")
      (node (ref "U2") (pin "55") (pinfunction "MIPI_TX1/RX1_D0P_55") (pintype "passive+no_connect"))
    )
    (net (code "163") (name "unconnected-(U2-MIPI_TX1{slash}RX1_D1N-Pad56)") (class "Default")
      (node (ref "U2") (pin "56") (pinfunction "MIPI_TX1/RX1_D1N_56") (pintype "passive+no_connect"))
    )
    (net (code "164") (name "unconnected-(U2-MIPI_TX1{slash}RX1_D1P-Pad57)") (class "Default")
      (node (ref "U2") (pin "57") (pinfunction "MIPI_TX1/RX1_D1P_57") (pintype "passive+no_connect"))
    )
    (net (code "165") (name "unconnected-(U2-MIPI_TX1{slash}RX1_D2N-Pad60)") (class "Default")
      (node (ref "U2") (pin "60") (pinfunction "MIPI_TX1/RX1_D2N_60") (pintype "passive+no_connect"))
    )
    (net (code "166") (name "unconnected-(U2-MIPI_TX1{slash}RX1_D2P-Pad61)") (class "Default")
      (node (ref "U2") (pin "61") (pinfunction "MIPI_TX1/RX1_D2P_61") (pintype "passive+no_connect"))
    )
    (net (code "167") (name "unconnected-(U2-MIPI_TX1{slash}RX1_D3N-Pad62)") (class "Default")
      (node (ref "U2") (pin "62") (pinfunction "MIPI_TX1/RX1_D3N_62") (pintype "passive+no_connect"))
    )
    (net (code "168") (name "unconnected-(U2-MIPI_TX1{slash}RX1_D3P-Pad63)") (class "Default")
      (node (ref "U2") (pin "63") (pinfunction "MIPI_TX1/RX1_D3P_63") (pintype "passive+no_connect"))
    )
    (net (code "169") (name "unconnected-(U2-MIPI_TX1{slash}RX1_D3P-Pad64)") (class "Default")
      (node (ref "U2") (pin "64") (pinfunction "MIPI_TX1/RX1_D3P_64") (pintype "passive+no_connect"))
    )
    (net (code "170") (name "unconnected-(U2-PCIE_REF_CLKN-Pad121)") (class "Default")
      (node (ref "U2") (pin "121") (pinfunction "PCIE_REF_CLKN_121") (pintype "passive+no_connect"))
    )
    (net (code "171") (name "unconnected-(U2-PCIE_REF_CLKP-Pad122)") (class "Default")
      (node (ref "U2") (pin "122") (pinfunction "PCIE_REF_CLKP_122") (pintype "passive+no_connect"))
    )
    (net (code "172") (name "unconnected-(U2-PCIE_RX0_N-Pad118)") (class "Default")
      (node (ref "U2") (pin "118") (pinfunction "PCIE_RX0_N_118") (pintype "passive+no_connect"))
    )
    (net (code "173") (name "unconnected-(U2-PCIE_RX0_P-Pad117)") (class "Default")
      (node (ref "U2") (pin "117") (pinfunction "PCIE_RX0_P_117") (pintype "passive+no_connect"))
    )
    (net (code "174") (name "unconnected-(U2-PCIE_TX0N-Pad120)") (class "Default")
      (node (ref "U2") (pin "120") (pinfunction "PCIE_TX0N_120") (pintype "passive+no_connect"))
    )
    (net (code "175") (name "unconnected-(U2-PCIE_TX0P-Pad119)") (class "Default")
      (node (ref "U2") (pin "119") (pinfunction "PCIE_TX0P_119") (pintype "passive+no_connect"))
    )
    (net (code "176") (name "unconnected-(U2-PMU_RESET-Pad28)") (class "Default")
      (node (ref "U2") (pin "28") (pinfunction "PMU_RESET_28") (pintype "passive+no_connect"))
    )
    (net (code "177") (name "unconnected-(U2-PORT_PHD-Pad49)") (class "Default")
      (node (ref "U2") (pin "49") (pinfunction "PORT_PHD_49") (pintype "passive+no_connect"))
    )
    (net (code "178") (name "unconnected-(U2-RTC_CLKO_WIFI-Pad33)") (class "Default")
      (node (ref "U2") (pin "33") (pinfunction "RTC_CLKO_WIFI_33") (pintype "passive+no_connect"))
    )
    (net (code "179") (name "unconnected-(U2-SDIO0_CLK-Pad22)") (class "Default")
      (node (ref "U2") (pin "22") (pinfunction "SDIO0_CLK_22") (pintype "passive+no_connect"))
    )
    (net (code "180") (name "unconnected-(U2-SDIO0_CMD-Pad21)") (class "Default")
      (node (ref "U2") (pin "21") (pinfunction "SDIO0_CMD_21") (pintype "passive+no_connect"))
    )
    (net (code "181") (name "unconnected-(U2-SDIO0_D0-Pad17)") (class "Default")
      (node (ref "U2") (pin "17") (pinfunction "SDIO0_D0_17") (pintype "passive+no_connect"))
    )
    (net (code "182") (name "unconnected-(U2-SDIO0_D1-Pad18)") (class "Default")
      (node (ref "U2") (pin "18") (pinfunction "SDIO0_D1_18") (pintype "passive+no_connect"))
    )
    (net (code "183") (name "unconnected-(U2-SDIO0_D2-Pad19)") (class "Default")
      (node (ref "U2") (pin "19") (pinfunction "SDIO0_D2_19") (pintype "passive+no_connect"))
    )
    (net (code "184") (name "unconnected-(U2-SDIO0_D3-Pad20)") (class "Default")
      (node (ref "U2") (pin "20") (pinfunction "SDIO0_D3_20") (pintype "passive+no_connect"))
    )
    (net (code "185") (name "unconnected-(U2-SDMMC0_CLK-Pad143)") (class "Default")
      (node (ref "U2") (pin "143") (pinfunction "SDMMC0_CLK_143") (pintype "passive+no_connect"))
    )
    (net (code "186") (name "unconnected-(U2-SDMMC0_CMD-Pad148)") (class "Default")
      (node (ref "U2") (pin "148") (pinfunction "SDMMC0_CMD_148") (pintype "passive+no_connect"))
    )
    (net (code "187") (name "unconnected-(U2-SDMMC0_D0-Pad147)") (class "Default")
      (node (ref "U2") (pin "147") (pinfunction "SDMMC0_D0_147") (pintype "passive+no_connect"))
    )
    (net (code "188") (name "unconnected-(U2-SDMMC0_D1-Pad146)") (class "Default")
      (node (ref "U2") (pin "146") (pinfunction "SDMMC0_D1_146") (pintype "passive+no_connect"))
    )
    (net (code "189") (name "unconnected-(U2-SDMMC0_D2-Pad145)") (class "Default")
      (node (ref "U2") (pin "145") (pinfunction "SDMMC0_D2_145") (pintype "passive+no_connect"))
    )
    (net (code "190") (name "unconnected-(U2-SDMMC0_D3-Pad144)") (class "Default")
      (node (ref "U2") (pin "144") (pinfunction "SDMMC0_D3_144") (pintype "passive+no_connect"))
    )
    (net (code "191") (name "unconnected-(U2-SDMMC0_DET_L-Pad149)") (class "Default")
      (node (ref "U2") (pin "149") (pinfunction "SDMMC0_DET_L_149") (pintype "passive+no_connect"))
    )
    (net (code "192") (name "unconnected-(U2-SDMMC0_PWR_H-Pad150)") (class "Default")
      (node (ref "U2") (pin "150") (pinfunction "SDMMC0_PWR_H_150") (pintype "passive+no_connect"))
    )
    (net (code "193") (name "unconnected-(U2-SPDIF_TX-Pad43)") (class "Default")
      (node (ref "U2") (pin "43") (pinfunction "SPDIF_TX_43") (pintype "passive"))
    )
    (net (code "194") (name "unconnected-(U2-TYPEC0_RX1N-Pad97)") (class "Default")
      (node (ref "U2") (pin "97") (pinfunction "TYPEC0_RX1N_97") (pintype "passive+no_connect"))
    )
    (net (code "195") (name "unconnected-(U2-TYPEC0_RX1P-Pad98)") (class "Default")
      (node (ref "U2") (pin "98") (pinfunction "TYPEC0_RX1P_98") (pintype "passive+no_connect"))
    )
    (net (code "196") (name "unconnected-(U2-TYPEC0_RX2N-Pad101)") (class "Default")
      (node (ref "U2") (pin "101") (pinfunction "TYPEC0_RX2N_101") (pintype "passive+no_connect"))
    )
    (net (code "197") (name "unconnected-(U2-TYPEC0_RX2P-Pad102)") (class "Default")
      (node (ref "U2") (pin "102") (pinfunction "TYPEC0_RX2P_102") (pintype "passive+no_connect"))
    )
    (net (code "198") (name "unconnected-(U2-TYPEC0_SBU1-Pad96)") (class "Default")
      (node (ref "U2") (pin "96") (pinfunction "TYPEC0_SBU1_96") (pintype "passive+no_connect"))
    )
    (net (code "199") (name "unconnected-(U2-TYPEC0_SBU1_DC-Pad93)") (class "Default")
      (node (ref "U2") (pin "93") (pinfunction "TYPEC0_SBU1_DC_93") (pintype "passive+no_connect"))
    )
    (net (code "200") (name "unconnected-(U2-TYPEC0_SBU2-Pad95)") (class "Default")
      (node (ref "U2") (pin "95") (pinfunction "TYPEC0_SBU2_95") (pintype "passive+no_connect"))
    )
    (net (code "201") (name "unconnected-(U2-TYPEC0_SBU2_DC-Pad94)") (class "Default")
      (node (ref "U2") (pin "94") (pinfunction "TYPEC0_SBU2_DC_94") (pintype "passive+no_connect"))
    )
    (net (code "202") (name "unconnected-(U2-TYPEC0_TX1N-Pad100)") (class "Default")
      (node (ref "U2") (pin "100") (pinfunction "TYPEC0_TX1N_100") (pintype "passive+no_connect"))
    )
    (net (code "203") (name "unconnected-(U2-TYPEC0_TX1P-Pad99)") (class "Default")
      (node (ref "U2") (pin "99") (pinfunction "TYPEC0_TX1P_99") (pintype "passive+no_connect"))
    )
    (net (code "204") (name "unconnected-(U2-TYPEC0_TX2N-Pad104)") (class "Default")
      (node (ref "U2") (pin "104") (pinfunction "TYPEC0_TX2N_104") (pintype "passive+no_connect"))
    )
    (net (code "205") (name "unconnected-(U2-TYPEC0_TX2P-Pad103)") (class "Default")
      (node (ref "U2") (pin "103") (pinfunction "TYPEC0_TX2P_103") (pintype "passive+no_connect"))
    )
    (net (code "206") (name "unconnected-(U2-UART0_CTS-Pad25)") (class "Default")
      (node (ref "U2") (pin "25") (pinfunction "UART0_CTS_25") (pintype "passive+no_connect"))
    )
    (net (code "207") (name "unconnected-(U2-UART0_RTS-Pad23)") (class "Default")
      (node (ref "U2") (pin "23") (pinfunction "UART0_RTS_23") (pintype "passive+no_connect"))
    )
    (net (code "208") (name "unconnected-(U2-USB3_DM-Pad111)") (class "Default")
      (node (ref "U2") (pin "111") (pinfunction "USB3_DM_111") (pintype "passive+no_connect"))
    )
    (net (code "209") (name "unconnected-(U2-USB3_DP-Pad112)") (class "Default")
      (node (ref "U2") (pin "112") (pinfunction "USB3_DP_112") (pintype "passive+no_connect"))
    )
    (net (code "210") (name "unconnected-(U2-USB3_SSRXN-Pad110)") (class "Default")
      (node (ref "U2") (pin "110") (pinfunction "USB3_SSRXN_110") (pintype "passive+no_connect"))
    )
    (net (code "211") (name "unconnected-(U2-USB3_SSRXP-Pad109)") (class "Default")
      (node (ref "U2") (pin "109") (pinfunction "USB3_SSRXP_109") (pintype "passive+no_connect"))
    )
    (net (code "212") (name "unconnected-(U2-USB3_SSTXN-Pad108)") (class "Default")
      (node (ref "U2") (pin "108") (pinfunction "USB3_SSTXN_108") (pintype "passive+no_connect"))
    )
    (net (code "213") (name "unconnected-(U2-USB3_SSTXP-Pad107)") (class "Default")
      (node (ref "U2") (pin "107") (pinfunction "USB3_SSTXP_107") (pintype "passive+no_connect"))
    )
    (net (code "214") (name "unconnected-(U3-NC-Pad6)") (class "Default")
      (node (ref "U3") (pin "6") (pinfunction "NC_6") (pintype "power_in+no_connect"))
    )
    (net (code "215") (name "unconnected-(U3-NC-Pad9)") (class "Default")
      (node (ref "U3") (pin "9") (pinfunction "NC_9") (pintype "power_in+no_connect"))
    )
    (net (code "216") (name "unconnected-(U4-NC-Pad6)") (class "Default")
      (node (ref "U4") (pin "6") (pinfunction "NC_6") (pintype "power_in+no_connect"))
    )
    (net (code "217") (name "unconnected-(U4-NC-Pad9)") (class "Default")
      (node (ref "U4") (pin "9") (pinfunction "NC_9") (pintype "power_in+no_connect"))
    )
    (net (code "218") (name "unconnected-(U5-NC-Pad6)") (class "Default")
      (node (ref "U5") (pin "6") (pinfunction "NC_6") (pintype "power_in+no_connect"))
    )
    (net (code "219") (name "unconnected-(U5-NC-Pad9)") (class "Default")
      (node (ref "U5") (pin "9") (pinfunction "NC_9") (pintype "power_in+no_connect"))
    )
  )
)
